# Maduino_Zero_Canbus_RS485_v1_1.net
KiCad netlist of a schematic drawn in EAGLE
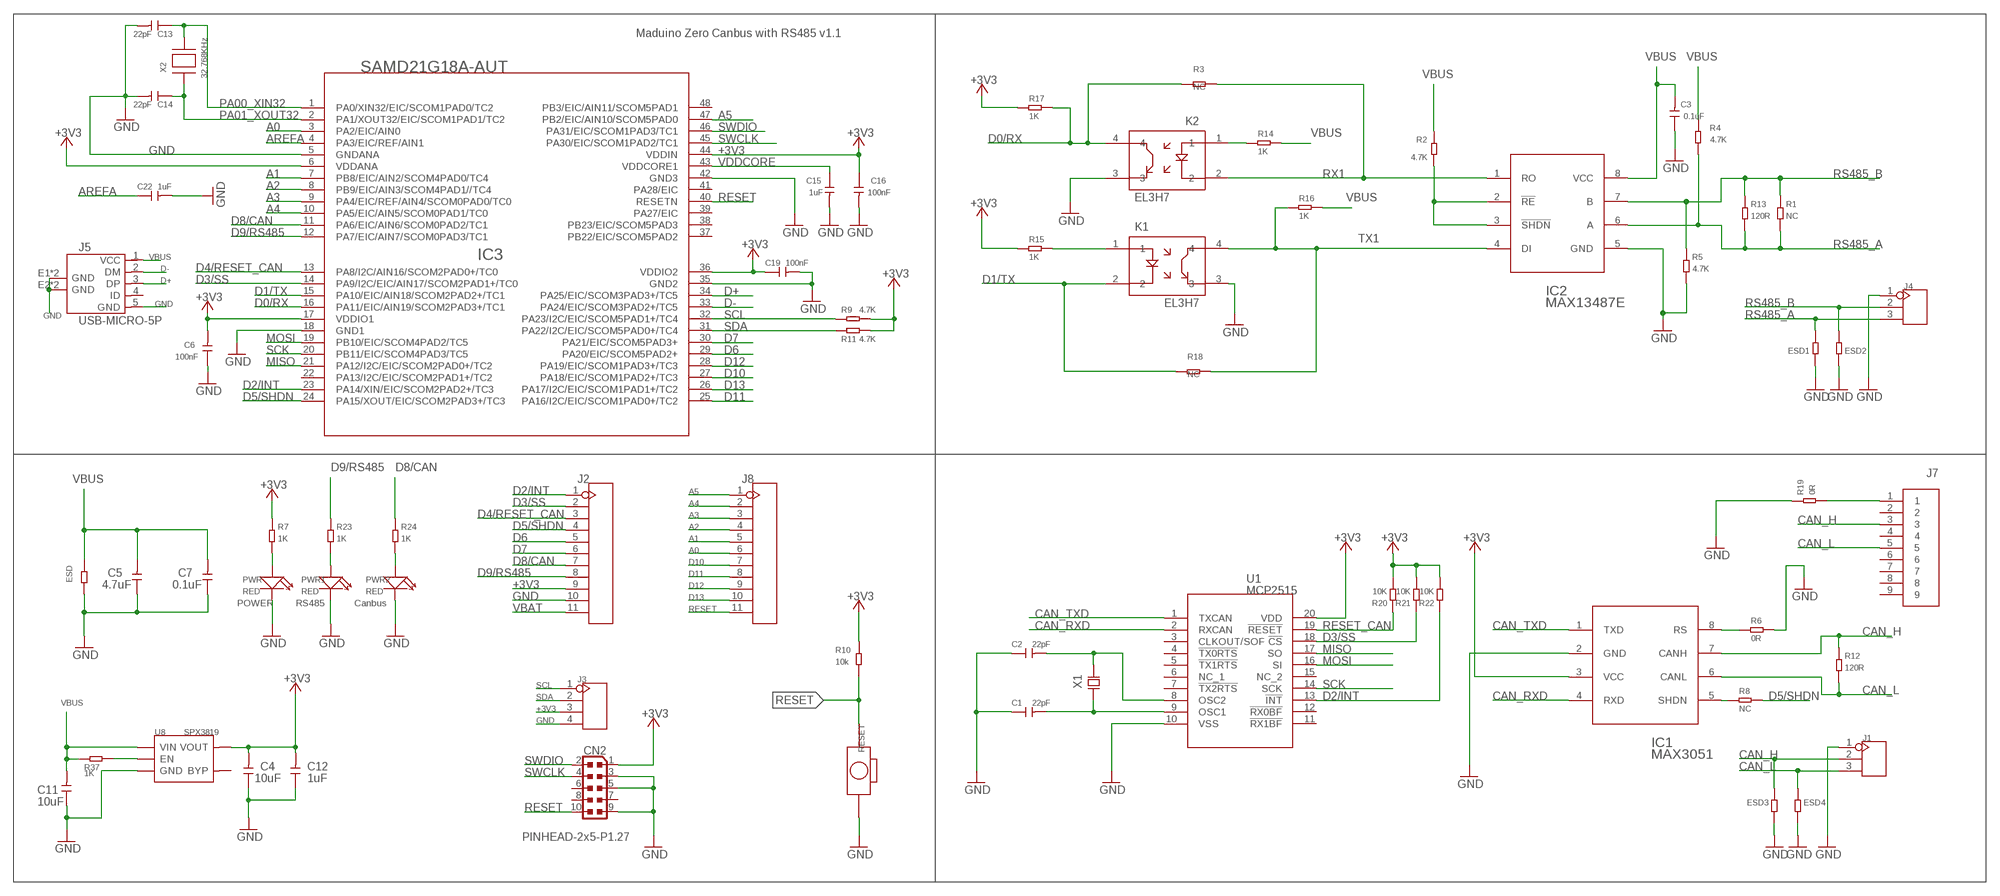
[diagram p0: schematic, sheet 1]

(export (version "E")
  (design (tool "Eeschema 10.0.6"))
  (components
    (comp (ref "C1")
      (value "22pF")
      (footprint "eagle-import:0603")
      (libsource (lib "eagle-import") (part "C-0603"))
    )
    (comp (ref "C2")
      (value "22pF")
      (footprint "eagle-import:0603")
      (libsource (lib "eagle-import") (part "C-0603"))
    )
    (comp (ref "C3")
      (value "0.1uF")
      (footprint "eagle-import:0603")
      (libsource (lib "eagle-import") (part "C-0603"))
    )
    (comp (ref "C4")
      (value "10uF")
      (footprint "eagle-import:0603")
      (libsource (lib "eagle-import") (part "C-0603"))
    )
    (comp (ref "C5")
      (value "4.7uF")
      (footprint "eagle-import:0603")
      (libsource (lib "eagle-import") (part "C-0603"))
    )
    (comp (ref "C6")
      (value "100nF")
      (footprint "eagle-import:0603")
      (libsource (lib "eagle-import") (part "C-0603"))
    )
    (comp (ref "C7")
      (value "0.1uF")
      (footprint "eagle-import:0603")
      (libsource (lib "eagle-import") (part "C-0603"))
    )
    (comp (ref "C11")
      (value "10uF")
      (footprint "eagle-import:0603")
      (libsource (lib "eagle-import") (part "C-0603"))
    )
    (comp (ref "C12")
      (value "1uF")
      (footprint "eagle-import:0603")
      (libsource (lib "eagle-import") (part "C-0603"))
    )
    (comp (ref "C13")
      (value "22pF")
      (footprint "eagle-import:0603")
      (libsource (lib "eagle-import") (part "C-0603"))
    )
    (comp (ref "C14")
      (value "22pF")
      (footprint "eagle-import:0603")
      (libsource (lib "eagle-import") (part "C-0603"))
    )
    (comp (ref "C15")
      (value "1uF")
      (footprint "eagle-import:0603")
      (libsource (lib "eagle-import") (part "C-0603"))
    )
    (comp (ref "C16")
      (value "100nF")
      (footprint "eagle-import:0603")
      (libsource (lib "eagle-import") (part "C-0603"))
    )
    (comp (ref "C19")
      (value "100nF")
      (footprint "eagle-import:0603")
      (libsource (lib "eagle-import") (part "C-0603"))
    )
    (comp (ref "C22")
      (value "1uF")
      (footprint "eagle-import:0603")
      (libsource (lib "eagle-import") (part "C-0603"))
    )
    (comp (ref "CN2")
      (value "PINHEAD-2x5-P1.27")
      (footprint "eagle-import:PINHEAD_2X05_127")
      (libsource (lib "eagle-import") (part "0171_PH127-205DF055G00AROUND-PADS"))
    )
    (comp (ref "ESD")
      (value "R-0603")
      (footprint "eagle-import:R0603")
      (libsource (lib "eagle-import") (part "R-0603"))
    )
    (comp (ref "ESD1")
      (value "R-0603")
      (footprint "eagle-import:R0603")
      (libsource (lib "eagle-import") (part "R-0603"))
    )
    (comp (ref "ESD2")
      (value "R-0603")
      (footprint "eagle-import:R0603")
      (libsource (lib "eagle-import") (part "R-0603"))
    )
    (comp (ref "ESD3")
      (value "NC")
      (footprint "eagle-import:R0603")
      (libsource (lib "eagle-import") (part "R-0603"))
    )
    (comp (ref "ESD4")
      (value "NC")
      (footprint "eagle-import:R0603")
      (libsource (lib "eagle-import") (part "R-0603"))
    )
    (comp (ref "IC1")
      (value "MAX3051")
      (footprint "eagle-import:DIP8_MX3051")
      (libsource (lib "eagle-import") (part "MAX3051"))
    )
    (comp (ref "IC2")
      (value "MAX13487E")
      (footprint "eagle-import:DIP8_MAX13487")
      (libsource (lib "eagle-import") (part "MAX13487E"))
    )
    (comp (ref "IC3")
      (value "SAMD21G18A-AUT")
      (footprint "eagle-import:TQFP48-7X7")
      (libsource (lib "eagle-import") (part "ATSAMD21G18A-AUT"))
    )
    (comp (ref "J1")
      (value "HEADER-3P-2.54")
      (footprint "eagle-import:3P-2.54")
      (libsource (lib "eagle-import") (part "HEADER-3P-2.54"))
    )
    (comp (ref "J2")
      (value "HEADER-11P-2.54")
      (footprint "eagle-import:11P-2.54")
      (libsource (lib "eagle-import") (part "HEADER-11P-2.54"))
    )
    (comp (ref "J3")
      (value "HEADER-4P-60/35MILROUND")
      (footprint "eagle-import:4P-65_35ROUND")
      (libsource (lib "eagle-import") (part "HEADER-4P-60/35MILROUND"))
    )
    (comp (ref "J4")
      (value "HEADER-3P-2.54")
      (footprint "eagle-import:3P-2.54")
      (libsource (lib "eagle-import") (part "HEADER-3P-2.54"))
    )
    (comp (ref "J5")
      (value "USB-MICRO-5P")
      (footprint "eagle-import:MICRO-USB-5P")
      (libsource (lib "eagle-import") (part "USB-MICRO-5P"))
    )
    (comp (ref "J7")
      (value "DB9-90")
      (footprint "eagle-import:DIP9-DB9-P2.77")
      (libsource (lib "eagle-import") (part "DB9-90"))
    )
    (comp (ref "J8")
      (value "HEADER-11P-2.54")
      (footprint "eagle-import:11P-2.54")
      (libsource (lib "eagle-import") (part "HEADER-11P-2.54"))
    )
    (comp (ref "K1")
      (value "EL3H7")
      (footprint "eagle-import:SOP-4_P1.27")
      (libsource (lib "eagle-import") (part "EL3H7"))
    )
    (comp (ref "K2")
      (value "EL3H7")
      (footprint "eagle-import:SOP-4_P1.27")
      (libsource (lib "eagle-import") (part "EL3H7"))
    )
    (comp (ref "PWR")
      (value "RED")
      (footprint "eagle-import:LED-0603")
      (libsource (lib "eagle-import") (part "LED'0603'"))
    )
    (comp (ref "PWR1")
      (value "RED")
      (footprint "eagle-import:LED-0603")
      (libsource (lib "eagle-import") (part "LED'0603'"))
    )
    (comp (ref "PWR2")
      (value "RED")
      (footprint "eagle-import:LED-0603")
      (libsource (lib "eagle-import") (part "LED'0603'"))
    )
    (comp (ref "R1")
      (value "NC")
      (footprint "eagle-import:R0603")
      (libsource (lib "eagle-import") (part "R-0603"))
    )
    (comp (ref "R2")
      (value "4.7K")
      (footprint "eagle-import:R0603")
      (libsource (lib "eagle-import") (part "R-0603"))
    )
    (comp (ref "R3")
      (value "NC")
      (footprint "eagle-import:R0603")
      (libsource (lib "eagle-import") (part "R-0603"))
    )
    (comp (ref "R4")
      (value "4.7K")
      (footprint "eagle-import:R0603")
      (libsource (lib "eagle-import") (part "R-0603"))
    )
    (comp (ref "R5")
      (value "4.7K")
      (footprint "eagle-import:R0603")
      (libsource (lib "eagle-import") (part "R-0603"))
    )
    (comp (ref "R6")
      (value "0R")
      (footprint "eagle-import:R0603")
      (libsource (lib "eagle-import") (part "R-0603"))
    )
    (comp (ref "R7")
      (value "1K")
      (footprint "eagle-import:R0603")
      (libsource (lib "eagle-import") (part "R-0603"))
    )
    (comp (ref "R8")
      (value "NC")
      (footprint "eagle-import:R0603")
      (libsource (lib "eagle-import") (part "R-0603"))
    )
    (comp (ref "R9")
      (value "4.7K")
      (footprint "eagle-import:R0603")
      (libsource (lib "eagle-import") (part "R-0603"))
    )
    (comp (ref "R10")
      (value "10k")
      (footprint "eagle-import:R0603")
      (libsource (lib "eagle-import") (part "R-0603"))
    )
    (comp (ref "R11")
      (value "4.7K")
      (footprint "eagle-import:R0603")
      (libsource (lib "eagle-import") (part "R-0603"))
    )
    (comp (ref "R12")
      (value "120R")
      (footprint "eagle-import:R0603")
      (libsource (lib "eagle-import") (part "R-0603"))
    )
    (comp (ref "R13")
      (value "120R")
      (footprint "eagle-import:R0603")
      (libsource (lib "eagle-import") (part "R-0603"))
    )
    (comp (ref "R14")
      (value "1K")
      (footprint "eagle-import:R0603")
      (libsource (lib "eagle-import") (part "R-0603"))
    )
    (comp (ref "R15")
      (value "1K")
      (footprint "eagle-import:R0603")
      (libsource (lib "eagle-import") (part "R-0603"))
    )
    (comp (ref "R16")
      (value "1K")
      (footprint "eagle-import:R0603")
      (libsource (lib "eagle-import") (part "R-0603"))
    )
    (comp (ref "R17")
      (value "1K")
      (footprint "eagle-import:R0603")
      (libsource (lib "eagle-import") (part "R-0603"))
    )
    (comp (ref "R18")
      (value "NC")
      (footprint "eagle-import:R0603")
      (libsource (lib "eagle-import") (part "R-0603"))
    )
    (comp (ref "R19")
      (value "0R")
      (footprint "eagle-import:R0603")
      (libsource (lib "eagle-import") (part "R-0603"))
    )
    (comp (ref "R20")
      (value "10K")
      (footprint "eagle-import:R0603")
      (libsource (lib "eagle-import") (part "R-0603"))
    )
    (comp (ref "R21")
      (value "10K")
      (footprint "eagle-import:R0603")
      (libsource (lib "eagle-import") (part "R-0603"))
    )
    (comp (ref "R22")
      (value "10K")
      (footprint "eagle-import:R0603")
      (libsource (lib "eagle-import") (part "R-0603"))
    )
    (comp (ref "R23")
      (value "1K")
      (footprint "eagle-import:R0603")
      (libsource (lib "eagle-import") (part "R-0603"))
    )
    (comp (ref "R24")
      (value "1K")
      (footprint "eagle-import:R0603")
      (libsource (lib "eagle-import") (part "R-0603"))
    )
    (comp (ref "R37")
      (value "1K")
      (footprint "eagle-import:R0603")
      (libsource (lib "eagle-import") (part "R-0603"))
    )
    (comp (ref "RESET")
      (value "BOTTON-2P-90D")
      (footprint "eagle-import:2P-7.62X3.56-90D")
      (libsource (lib "eagle-import") (part "BOTTON-2P-90D"))
    )
    (comp (ref "U1")
      (value "MCP2515")
      (footprint "eagle-import:SSOP-20")
      (libsource (lib "eagle-import") (part "MCP2515"))
    )
    (comp (ref "U8")
      (value "SPX3819")
      (footprint "eagle-import:SOT23-5")
      (libsource (lib "eagle-import") (part "SPX3819"))
    )
    (comp (ref "X1")
      (value "XTAL-8MHZ")
      (footprint "eagle-import:SMD-5032_2P_8M")
      (libsource (lib "eagle-import") (part "XTAL-8MHZ"))
    )
    (comp (ref "X2")
      (value "32.768KHz")
      (footprint "eagle-import:XTAL3215")
      (libsource (lib "eagle-import") (part "XTAL-3.2X1.5"))
    )
  )
  (nets
    (net (code "1") (name "+3V3") (class "Default")
      (node (ref "C12") (pin "2") (pinfunction "2_2") (pintype "passive"))
      (node (ref "C16") (pin "1") (pinfunction "1_1") (pintype "passive"))
      (node (ref "C19") (pin "1") (pinfunction "1_1") (pintype "passive"))
      (node (ref "C4") (pin "2") (pinfunction "2_2") (pintype "passive"))
      (node (ref "C6") (pin "2") (pinfunction "2_2") (pintype "passive"))
      (node (ref "CN2") (pin "1") (pinfunction "1_1") (pintype "passive"))
      (node (ref "IC1") (pin "3") (pinfunction "VCC_3") (pintype "bidirectional"))
      (node (ref "IC3") (pin "17") (pinfunction "VDDIO1_17") (pintype "power_in"))
      (node (ref "IC3") (pin "36") (pinfunction "VDDIO2_36") (pintype "power_in"))
      (node (ref "IC3") (pin "44") (pinfunction "VDDIN_44") (pintype "power_in"))
      (node (ref "IC3") (pin "6") (pinfunction "VDDANA_6") (pintype "power_in"))
      (node (ref "J2") (pin "9") (pinfunction "9_9") (pintype "bidirectional"))
      (node (ref "J3") (pin "3") (pinfunction "P$3_3") (pintype "bidirectional"))
      (node (ref "R10") (pin "2") (pinfunction "2_2") (pintype "passive"))
      (node (ref "R11") (pin "2") (pinfunction "2_2") (pintype "passive"))
      (node (ref "R15") (pin "2") (pinfunction "2_2") (pintype "passive"))
      (node (ref "R17") (pin "2") (pinfunction "2_2") (pintype "passive"))
      (node (ref "R20") (pin "1") (pinfunction "1_1") (pintype "passive"))
      (node (ref "R21") (pin "1") (pinfunction "1_1") (pintype "passive"))
      (node (ref "R22") (pin "1") (pinfunction "1_1") (pintype "passive"))
      (node (ref "R7") (pin "1") (pinfunction "1_1") (pintype "passive"))
      (node (ref "R9") (pin "2") (pinfunction "2_2") (pintype "passive"))
      (node (ref "U1") (pin "20") (pinfunction "VDD_20") (pintype "bidirectional"))
      (node (ref "U8") (pin "5") (pinfunction "VOUT_5") (pintype "bidirectional"))
    )
    (net (code "2") (name "/A0") (class "Default")
      (node (ref "IC3") (pin "3") (pinfunction "PA2/EIC/AIN0_3") (pintype "bidirectional"))
      (node (ref "J8") (pin "6") (pinfunction "6_6") (pintype "bidirectional"))
    )
    (net (code "3") (name "/A1") (class "Default")
      (node (ref "IC3") (pin "7") (pinfunction "PB8/EIC/AIN2/SCOM4PAD0/TC4_7") (pintype "bidirectional"))
      (node (ref "J8") (pin "5") (pinfunction "5_5") (pintype "bidirectional"))
    )
    (net (code "4") (name "/A2") (class "Default")
      (node (ref "IC3") (pin "8") (pinfunction "PB9/EIC/AIN3/SCOM4PAD1//TC4_8") (pintype "bidirectional"))
      (node (ref "J8") (pin "4") (pinfunction "4_4") (pintype "bidirectional"))
    )
    (net (code "5") (name "/A3") (class "Default")
      (node (ref "IC3") (pin "9") (pinfunction "PA4/EIC/REF/AIN4/SCOM0PAD0/TC0_9") (pintype "bidirectional"))
      (node (ref "J8") (pin "3") (pinfunction "3_3") (pintype "bidirectional"))
    )
    (net (code "6") (name "/A4") (class "Default")
      (node (ref "IC3") (pin "10") (pinfunction "PA5/EIC/AIN5/SCOM0PAD1/TC0_10") (pintype "bidirectional"))
      (node (ref "J8") (pin "2") (pinfunction "2_2") (pintype "bidirectional"))
    )
    (net (code "7") (name "/A5") (class "Default")
      (node (ref "IC3") (pin "47") (pinfunction "PB2/EIC/AIN10/SCOM5PAD0_47") (pintype "bidirectional"))
      (node (ref "J8") (pin "1") (pinfunction "1_1") (pintype "bidirectional"))
    )
    (net (code "8") (name "/AREFA") (class "Default")
      (node (ref "C22") (pin "1") (pinfunction "1_1") (pintype "passive"))
      (node (ref "IC3") (pin "4") (pinfunction "PA3/EIC/REF/AIN1_4") (pintype "bidirectional"))
    )
    (net (code "9") (name "/CAN_H") (class "Default")
      (node (ref "ESD3") (pin "1") (pinfunction "1_1") (pintype "passive"))
      (node (ref "IC1") (pin "7") (pinfunction "CANH_7") (pintype "bidirectional"))
      (node (ref "J1") (pin "2") (pinfunction "P$2_2") (pintype "bidirectional"))
      (node (ref "J7") (pin "3") (pinfunction "3_3") (pintype "bidirectional"))
      (node (ref "R12") (pin "1") (pinfunction "1_1") (pintype "passive"))
    )
    (net (code "10") (name "/CAN_L") (class "Default")
      (node (ref "ESD4") (pin "1") (pinfunction "1_1") (pintype "passive"))
      (node (ref "IC1") (pin "6") (pinfunction "CANL_6") (pintype "bidirectional"))
      (node (ref "J1") (pin "3") (pinfunction "P$3_3") (pintype "bidirectional"))
      (node (ref "J7") (pin "5") (pinfunction "5_5") (pintype "bidirectional"))
      (node (ref "R12") (pin "2") (pinfunction "2_2") (pintype "passive"))
    )
    (net (code "11") (name "/CAN_RXD") (class "Default")
      (node (ref "IC1") (pin "4") (pinfunction "RXD_4") (pintype "bidirectional"))
      (node (ref "U1") (pin "2") (pinfunction "RXCAN_2") (pintype "bidirectional"))
    )
    (net (code "12") (name "/CAN_TXD") (class "Default")
      (node (ref "IC1") (pin "1") (pinfunction "TXD_1") (pintype "bidirectional"))
      (node (ref "U1") (pin "1") (pinfunction "TXCAN_1") (pintype "bidirectional"))
    )
    (net (code "13") (name "/D+") (class "Default")
      (node (ref "IC3") (pin "34") (pinfunction "PA25/EIC/SCOM3PAD3+/TC5_34") (pintype "bidirectional"))
      (node (ref "J5") (pin "3") (pinfunction "DP_3") (pintype "bidirectional"))
    )
    (net (code "14") (name "/D-") (class "Default")
      (node (ref "IC3") (pin "33") (pinfunction "PA24/EIC/SCOM3PAD2+/TC5_33") (pintype "bidirectional"))
      (node (ref "J5") (pin "2") (pinfunction "DM_2") (pintype "bidirectional"))
    )
    (net (code "15") (name "/D0{slash}RX") (class "Default")
      (node (ref "IC3") (pin "16") (pinfunction "PA11/EIC/AIN19/SCOM2PAD3+/TC1_16") (pintype "bidirectional"))
      (node (ref "K2") (pin "4") (pinfunction "4_4") (pintype "bidirectional"))
      (node (ref "R17") (pin "1") (pinfunction "1_1") (pintype "passive"))
      (node (ref "R3") (pin "2") (pinfunction "2_2") (pintype "passive"))
    )
    (net (code "16") (name "/D1{slash}TX") (class "Default")
      (node (ref "IC3") (pin "15") (pinfunction "PA10/EIC/AIN18/SCOM2PAD2+/TC1_15") (pintype "bidirectional"))
      (node (ref "K1") (pin "2") (pinfunction "2_2") (pintype "bidirectional"))
      (node (ref "R18") (pin "2") (pinfunction "2_2") (pintype "passive"))
    )
    (net (code "17") (name "/D2{slash}INT") (class "Default")
      (node (ref "IC3") (pin "23") (pinfunction "PA14/XIN/EIC/SCOM2PAD2+/TC3_23") (pintype "bidirectional"))
      (node (ref "J2") (pin "1") (pinfunction "1_1") (pintype "bidirectional"))
      (node (ref "R22") (pin "2") (pinfunction "2_2") (pintype "passive"))
      (node (ref "U1") (pin "13") (pinfunction "~{INT}_13") (pintype "bidirectional"))
    )
    (net (code "18") (name "/D3{slash}SS") (class "Default")
      (node (ref "IC3") (pin "14") (pinfunction "PA9/I2C/EIC/AIN17/SCOM2PAD1+/TC0_14") (pintype "bidirectional"))
      (node (ref "J2") (pin "2") (pinfunction "2_2") (pintype "bidirectional"))
      (node (ref "R21") (pin "2") (pinfunction "2_2") (pintype "passive"))
      (node (ref "U1") (pin "18") (pinfunction "~{CS}_18") (pintype "bidirectional"))
    )
    (net (code "19") (name "/D4{slash}RESET_CAN") (class "Default")
      (node (ref "IC3") (pin "13") (pinfunction "PA8/I2C/AIN16/SCOM2PAD0+/TC0_13") (pintype "bidirectional"))
      (node (ref "J2") (pin "3") (pinfunction "3_3") (pintype "bidirectional"))
    )
    (net (code "20") (name "/D5{slash}SHDN") (class "Default")
      (node (ref "IC3") (pin "24") (pinfunction "PA15/XOUT/EIC/SCOM2PAD3+/TC3_24") (pintype "bidirectional"))
      (node (ref "J2") (pin "4") (pinfunction "4_4") (pintype "bidirectional"))
      (node (ref "R8") (pin "1") (pinfunction "1_1") (pintype "passive"))
    )
    (net (code "21") (name "/D6") (class "Default")
      (node (ref "IC3") (pin "29") (pinfunction "PA20/EIC/SCOM5PAD2+_29") (pintype "bidirectional"))
      (node (ref "J2") (pin "5") (pinfunction "5_5") (pintype "bidirectional"))
    )
    (net (code "22") (name "/D7") (class "Default")
      (node (ref "IC3") (pin "30") (pinfunction "PA21/EIC/SCOM5PAD3+_30") (pintype "bidirectional"))
      (node (ref "J2") (pin "6") (pinfunction "6_6") (pintype "bidirectional"))
    )
    (net (code "23") (name "/D8{slash}CAN") (class "Default")
      (node (ref "IC3") (pin "11") (pinfunction "PA6/EIC/AIN6/SCOM0PAD2/TC1_11") (pintype "bidirectional"))
      (node (ref "J2") (pin "7") (pinfunction "7_7") (pintype "bidirectional"))
      (node (ref "R24") (pin "1") (pinfunction "1_1") (pintype "passive"))
    )
    (net (code "24") (name "/D9{slash}RS485") (class "Default")
      (node (ref "IC3") (pin "12") (pinfunction "PA7/EIC/AIN7/SCOM0PAD3/TC1_12") (pintype "bidirectional"))
      (node (ref "J2") (pin "8") (pinfunction "8_8") (pintype "bidirectional"))
      (node (ref "R23") (pin "1") (pinfunction "1_1") (pintype "passive"))
    )
    (net (code "25") (name "/D10") (class "Default")
      (node (ref "IC3") (pin "27") (pinfunction "PA18/EIC/SCOM1PAD2+/TC3_27") (pintype "bidirectional"))
      (node (ref "J8") (pin "7") (pinfunction "7_7") (pintype "bidirectional"))
    )
    (net (code "26") (name "/D11") (class "Default")
      (node (ref "IC3") (pin "25") (pinfunction "PA16/I2C/EIC/SCOM1PAD0+/TC2_25") (pintype "bidirectional"))
      (node (ref "J8") (pin "8") (pinfunction "8_8") (pintype "bidirectional"))
    )
    (net (code "27") (name "/D12") (class "Default")
      (node (ref "IC3") (pin "28") (pinfunction "PA19/EIC/SCOM1PAD3+/TC3_28") (pintype "bidirectional"))
      (node (ref "J8") (pin "9") (pinfunction "9_9") (pintype "bidirectional"))
    )
    (net (code "28") (name "/D13") (class "Default")
      (node (ref "IC3") (pin "26") (pinfunction "PA17/I2C/EIC/SCOM1PAD1+/TC2_26") (pintype "bidirectional"))
      (node (ref "J8") (pin "10") (pinfunction "10_10") (pintype "bidirectional"))
    )
    (net (code "29") (name "/MISO") (class "Default")
      (node (ref "IC3") (pin "21") (pinfunction "PA12/I2C/EIC/SCOM2PAD0+/TC2_21") (pintype "bidirectional"))
      (node (ref "U1") (pin "17") (pinfunction "SO_17") (pintype "bidirectional"))
    )
    (net (code "30") (name "/MOSI") (class "Default")
      (node (ref "IC3") (pin "19") (pinfunction "PB10/EIC/SCOM4PAD2/TC5_19") (pintype "bidirectional"))
      (node (ref "U1") (pin "16") (pinfunction "SI_16") (pintype "bidirectional"))
    )
    (net (code "31") (name "/PA00_XIN32") (class "Default")
      (node (ref "C13") (pin "1") (pinfunction "1_1") (pintype "passive"))
      (node (ref "IC3") (pin "1") (pinfunction "PA0/XIN32/EIC/SCOM1PAD0/TC2_1") (pintype "bidirectional"))
      (node (ref "X2") (pin "P$2") (pinfunction "P$2_P$2") (pintype "bidirectional"))
    )
    (net (code "32") (name "/PA01_XOUT32") (class "Default")
      (node (ref "C14") (pin "1") (pinfunction "1_1") (pintype "passive"))
      (node (ref "IC3") (pin "2") (pinfunction "PA1/XOUT32/EIC/SCOM1PAD1/TC2_2") (pintype "bidirectional"))
      (node (ref "X2") (pin "P$1") (pinfunction "P$1_P$1") (pintype "bidirectional"))
    )
    (net (code "33") (name "/RESET_CAN") (class "Default")
      (node (ref "R20") (pin "2") (pinfunction "2_2") (pintype "passive"))
      (node (ref "U1") (pin "19") (pinfunction "~{RESET}_19") (pintype "bidirectional"))
    )
    (net (code "34") (name "/RS485_A") (class "Default")
      (node (ref "ESD1") (pin "2") (pinfunction "2_2") (pintype "passive"))
      (node (ref "IC2") (pin "6") (pinfunction "A_6") (pintype "bidirectional"))
      (node (ref "J4") (pin "3") (pinfunction "P$3_3") (pintype "bidirectional"))
      (node (ref "R1") (pin "1") (pinfunction "1_1") (pintype "passive"))
      (node (ref "R13") (pin "1") (pinfunction "1_1") (pintype "passive"))
      (node (ref "R4") (pin "1") (pinfunction "1_1") (pintype "passive"))
    )
    (net (code "35") (name "/RS485_B") (class "Default")
      (node (ref "ESD2") (pin "2") (pinfunction "2_2") (pintype "passive"))
      (node (ref "IC2") (pin "7") (pinfunction "B_7") (pintype "bidirectional"))
      (node (ref "J4") (pin "2") (pinfunction "P$2_2") (pintype "bidirectional"))
      (node (ref "R1") (pin "2") (pinfunction "2_2") (pintype "passive"))
      (node (ref "R13") (pin "2") (pinfunction "2_2") (pintype "passive"))
      (node (ref "R5") (pin "2") (pinfunction "2_2") (pintype "passive"))
    )
    (net (code "36") (name "/RX1") (class "Default")
      (node (ref "IC2") (pin "1") (pinfunction "RO_1") (pintype "bidirectional"))
      (node (ref "K2") (pin "2") (pinfunction "2_2") (pintype "bidirectional"))
      (node (ref "R3") (pin "1") (pinfunction "1_1") (pintype "passive"))
    )
    (net (code "37") (name "/SCK") (class "Default")
      (node (ref "IC3") (pin "20") (pinfunction "PB11/EIC/SCOM4PAD3/TC5_20") (pintype "bidirectional"))
      (node (ref "U1") (pin "14") (pinfunction "SCK_14") (pintype "bidirectional"))
    )
    (net (code "38") (name "/SCL") (class "Default")
      (node (ref "IC3") (pin "32") (pinfunction "PA23/I2C/EIC/SCOM5PAD1+/TC4_32") (pintype "bidirectional"))
      (node (ref "J3") (pin "1") (pinfunction "P$1_1") (pintype "bidirectional"))
      (node (ref "R9") (pin "1") (pinfunction "1_1") (pintype "passive"))
    )
    (net (code "39") (name "/SDA") (class "Default")
      (node (ref "IC3") (pin "31") (pinfunction "PA22/I2C/EIC/SCOM5PAD0+/TC4_31") (pintype "bidirectional"))
      (node (ref "J3") (pin "2") (pinfunction "P$2_2") (pintype "bidirectional"))
      (node (ref "R11") (pin "1") (pinfunction "1_1") (pintype "passive"))
    )
    (net (code "40") (name "/SWCLK") (class "Default")
      (node (ref "CN2") (pin "4") (pinfunction "4_4") (pintype "passive"))
      (node (ref "IC3") (pin "45") (pinfunction "PA30/EIC/SCOM1PAD2/TC1_45") (pintype "bidirectional"))
    )
    (net (code "41") (name "/SWDIO") (class "Default")
      (node (ref "CN2") (pin "2") (pinfunction "2_2") (pintype "passive"))
      (node (ref "IC3") (pin "46") (pinfunction "PA31/EIC/SCOM1PAD3/TC1_46") (pintype "bidirectional"))
    )
    (net (code "42") (name "/TX1") (class "Default")
      (node (ref "IC2") (pin "4") (pinfunction "DI_4") (pintype "bidirectional"))
      (node (ref "K1") (pin "4") (pinfunction "4_4") (pintype "bidirectional"))
      (node (ref "R16") (pin "2") (pinfunction "2_2") (pintype "passive"))
      (node (ref "R18") (pin "1") (pinfunction "1_1") (pintype "passive"))
    )
    (net (code "43") (name "/VBAT") (class "Default")
      (node (ref "J2") (pin "11") (pinfunction "11_11") (pintype "bidirectional"))
    )
    (net (code "44") (name "/VBUS") (class "Default")
      (node (ref "C11") (pin "2") (pinfunction "2_2") (pintype "passive"))
      (node (ref "C3") (pin "2") (pinfunction "2_2") (pintype "passive"))
      (node (ref "C5") (pin "2") (pinfunction "2_2") (pintype "passive"))
      (node (ref "C7") (pin "2") (pinfunction "2_2") (pintype "passive"))
      (node (ref "ESD") (pin "1") (pinfunction "1_1") (pintype "passive"))
      (node (ref "IC2") (pin "8") (pinfunction "VCC_8") (pintype "bidirectional"))
      (node (ref "J5") (pin "1") (pinfunction "VCC_1") (pintype "bidirectional"))
      (node (ref "R14") (pin "1") (pinfunction "1_1") (pintype "passive"))
      (node (ref "R16") (pin "1") (pinfunction "1_1") (pintype "passive"))
      (node (ref "R2") (pin "2") (pinfunction "2_2") (pintype "passive"))
      (node (ref "R37") (pin "1") (pinfunction "1_1") (pintype "passive"))
      (node (ref "R4") (pin "2") (pinfunction "2_2") (pintype "passive"))
      (node (ref "U8") (pin "1") (pinfunction "VIN_1") (pintype "bidirectional"))
    )
    (net (code "45") (name "/VDDCORE") (class "Default")
      (node (ref "C15") (pin "1") (pinfunction "1_1") (pintype "passive"))
      (node (ref "IC3") (pin "43") (pinfunction "VDDCORE1_43") (pintype "input"))
    )
    (net (code "46") (name "GND") (class "Default")
      (node (ref "C1") (pin "1") (pinfunction "1_1") (pintype "passive"))
      (node (ref "C11") (pin "1") (pinfunction "1_1") (pintype "passive"))
      (node (ref "C12") (pin "1") (pinfunction "1_1") (pintype "passive"))
      (node (ref "C13") (pin "2") (pinfunction "2_2") (pintype "passive"))
      (node (ref "C14") (pin "2") (pinfunction "2_2") (pintype "passive"))
      (node (ref "C15") (pin "2") (pinfunction "2_2") (pintype "passive"))
      (node (ref "C16") (pin "2") (pinfunction "2_2") (pintype "passive"))
      (node (ref "C19") (pin "2") (pinfunction "2_2") (pintype "passive"))
      (node (ref "C2") (pin "1") (pinfunction "1_1") (pintype "passive"))
      (node (ref "C22") (pin "2") (pinfunction "2_2") (pintype "passive"))
      (node (ref "C3") (pin "1") (pinfunction "1_1") (pintype "passive"))
      (node (ref "C4") (pin "1") (pinfunction "1_1") (pintype "passive"))
      (node (ref "C5") (pin "1") (pinfunction "1_1") (pintype "passive"))
      (node (ref "C6") (pin "1") (pinfunction "1_1") (pintype "passive"))
      (node (ref "C7") (pin "1") (pinfunction "1_1") (pintype "passive"))
      (node (ref "CN2") (pin "3") (pinfunction "3_3") (pintype "passive"))
      (node (ref "CN2") (pin "5") (pinfunction "5_5") (pintype "passive"))
      (node (ref "CN2") (pin "9") (pinfunction "9_9") (pintype "passive"))
      (node (ref "ESD") (pin "2") (pinfunction "2_2") (pintype "passive"))
      (node (ref "ESD1") (pin "1") (pinfunction "1_1") (pintype "passive"))
      (node (ref "ESD2") (pin "1") (pinfunction "1_1") (pintype "passive"))
      (node (ref "ESD3") (pin "2") (pinfunction "2_2") (pintype "passive"))
      (node (ref "ESD4") (pin "2") (pinfunction "2_2") (pintype "passive"))
      (node (ref "IC1") (pin "2") (pinfunction "GND_2") (pintype "bidirectional"))
      (node (ref "IC2") (pin "5") (pinfunction "GND_5") (pintype "bidirectional"))
      (node (ref "IC3") (pin "18") (pinfunction "GND1_18") (pintype "power_in"))
      (node (ref "IC3") (pin "35") (pinfunction "GND2_35") (pintype "power_in"))
      (node (ref "IC3") (pin "42") (pinfunction "GND3_42") (pintype "power_in"))
      (node (ref "IC3") (pin "5") (pinfunction "GNDANA_5") (pintype "power_in"))
      (node (ref "J1") (pin "1") (pinfunction "P$1_1") (pintype "bidirectional"))
      (node (ref "J2") (pin "10") (pinfunction "10_10") (pintype "bidirectional"))
      (node (ref "J3") (pin "4") (pinfunction "P$4_4") (pintype "bidirectional"))
      (node (ref "J4") (pin "1") (pinfunction "P$1_1") (pintype "bidirectional"))
      (node (ref "J5") (pin "5") (pinfunction "GND_5") (pintype "bidirectional"))
      (node (ref "J5") (pin "E1") (pinfunction "GND_E1") (pintype "bidirectional"))
      (node (ref "J5") (pin "E2") (pinfunction "GND_E2") (pintype "bidirectional"))
      (node (ref "J5") (pin "P1") (pinfunction "GND_P1") (pintype "bidirectional"))
      (node (ref "J5") (pin "P2") (pinfunction "GND_P2") (pintype "bidirectional"))
      (node (ref "K1") (pin "3") (pinfunction "3_3") (pintype "bidirectional"))
      (node (ref "K2") (pin "3") (pinfunction "3_3") (pintype "bidirectional"))
      (node (ref "PWR") (pin "-") (pinfunction "-_-") (pintype "passive"))
      (node (ref "PWR1") (pin "-") (pinfunction "-_-") (pintype "passive"))
      (node (ref "PWR2") (pin "-") (pinfunction "-_-") (pintype "passive"))
      (node (ref "R19") (pin "2") (pinfunction "2_2") (pintype "passive"))
      (node (ref "R5") (pin "1") (pinfunction "1_1") (pintype "passive"))
      (node (ref "R6") (pin "1") (pinfunction "1_1") (pintype "passive"))
      (node (ref "RESET") (pin "P$2") (pinfunction "2_P$2") (pintype "bidirectional"))
      (node (ref "U1") (pin "10") (pinfunction "VSS_10") (pintype "bidirectional"))
      (node (ref "U8") (pin "2") (pinfunction "GND_2") (pintype "bidirectional"))
    )
    (net (code "47") (name "Net-(IC1-RS)") (class "Default")
      (node (ref "IC1") (pin "8") (pinfunction "RS_8") (pintype "bidirectional"))
      (node (ref "R6") (pin "2") (pinfunction "2_2") (pintype "passive"))
    )
    (net (code "48") (name "Net-(IC1-SHDN)") (class "Default")
      (node (ref "IC1") (pin "5") (pinfunction "SHDN_5") (pintype "bidirectional"))
      (node (ref "R8") (pin "2") (pinfunction "2_2") (pintype "passive"))
    )
    (net (code "49") (name "Net-(IC2-~{RE})") (class "Default")
      (node (ref "IC2") (pin "2") (pinfunction "~{RE}_2") (pintype "bidirectional"))
      (node (ref "IC2") (pin "3") (pinfunction "~{SHDN}_3") (pintype "bidirectional"))
      (node (ref "R2") (pin "1") (pinfunction "1_1") (pintype "passive"))
    )
    (net (code "50") (name "Net-(J7-Pad1)") (class "Default")
      (node (ref "J7") (pin "1") (pinfunction "1_1") (pintype "bidirectional"))
      (node (ref "R19") (pin "1") (pinfunction "1_1") (pintype "passive"))
    )
    (net (code "51") (name "Net-(K1-Pad1)") (class "Default")
      (node (ref "K1") (pin "1") (pinfunction "1_1") (pintype "bidirectional"))
      (node (ref "R15") (pin "1") (pinfunction "1_1") (pintype "passive"))
    )
    (net (code "52") (name "Net-(K2-Pad1)") (class "Default")
      (node (ref "K2") (pin "1") (pinfunction "1_1") (pintype "bidirectional"))
      (node (ref "R14") (pin "2") (pinfunction "2_2") (pintype "passive"))
    )
    (net (code "53") (name "Net-(PWR-Pad+)") (class "Default")
      (node (ref "PWR") (pin "+") (pinfunction "+_+") (pintype "passive"))
      (node (ref "R7") (pin "2") (pinfunction "2_2") (pintype "passive"))
    )
    (net (code "54") (name "Net-(PWR1-Pad+)") (class "Default")
      (node (ref "PWR1") (pin "+") (pinfunction "+_+") (pintype "passive"))
      (node (ref "R23") (pin "2") (pinfunction "2_2") (pintype "passive"))
    )
    (net (code "55") (name "Net-(PWR2-Pad+)") (class "Default")
      (node (ref "PWR2") (pin "+") (pinfunction "+_+") (pintype "passive"))
      (node (ref "R24") (pin "2") (pinfunction "2_2") (pintype "passive"))
    )
    (net (code "56") (name "Net-(U1-OSC1)") (class "Default")
      (node (ref "C1") (pin "2") (pinfunction "2_2") (pintype "passive"))
      (node (ref "U1") (pin "9") (pinfunction "OSC1_9") (pintype "bidirectional"))
      (node (ref "X1") (pin "1") (pinfunction "1_1") (pintype "bidirectional"))
    )
    (net (code "57") (name "Net-(U1-OSC2)") (class "Default")
      (node (ref "C2") (pin "2") (pinfunction "2_2") (pintype "passive"))
      (node (ref "U1") (pin "8") (pinfunction "OSC2_8") (pintype "bidirectional"))
      (node (ref "X1") (pin "2") (pinfunction "2_2") (pintype "bidirectional"))
    )
    (net (code "58") (name "Net-(U8-EN)") (class "Default")
      (node (ref "R37") (pin "2") (pinfunction "2_2") (pintype "passive"))
      (node (ref "U8") (pin "3") (pinfunction "EN_3") (pintype "bidirectional"))
    )
    (net (code "59") (name "RESET") (class "Default")
      (node (ref "CN2") (pin "10") (pinfunction "10_10") (pintype "passive"))
      (node (ref "IC3") (pin "40") (pinfunction "RESETN_40") (pintype "bidirectional"))
      (node (ref "J8") (pin "11") (pinfunction "11_11") (pintype "bidirectional"))
      (node (ref "R10") (pin "1") (pinfunction "1_1") (pintype "passive"))
      (node (ref "RESET") (pin "P$1") (pinfunction "1_P$1") (pintype "bidirectional"))
    )
    (net (code "60") (name "unconnected-(CN2-Pad6)") (class "Default")
      (node (ref "CN2") (pin "6") (pinfunction "6_6") (pintype "passive"))
    )
    (net (code "61") (name "unconnected-(CN2-Pad7)") (class "Default")
      (node (ref "CN2") (pin "7") (pinfunction "7_7") (pintype "passive"))
    )
    (net (code "62") (name "unconnected-(CN2-Pad8)") (class "Default")
      (node (ref "CN2") (pin "8") (pinfunction "8_8") (pintype "passive"))
    )
    (net (code "63") (name "unconnected-(IC3-PA13{slash}I2C{slash}EIC{slash}SCOM2PAD1+{slash}TC2-Pad22)") (class "Default")
      (node (ref "IC3") (pin "22") (pinfunction "PA13/I2C/EIC/SCOM2PAD1+/TC2_22") (pintype "bidirectional"))
    )
    (net (code "64") (name "unconnected-(IC3-PA27{slash}EIC-Pad39)") (class "Default")
      (node (ref "IC3") (pin "39") (pinfunction "PA27/EIC_39") (pintype "bidirectional"))
    )
    (net (code "65") (name "unconnected-(IC3-PA28{slash}EIC-Pad41)") (class "Default")
      (node (ref "IC3") (pin "41") (pinfunction "PA28/EIC_41") (pintype "bidirectional"))
    )
    (net (code "66") (name "unconnected-(IC3-PB3{slash}EIC{slash}AIN11{slash}SCOM5PAD1-Pad48)") (class "Default")
      (node (ref "IC3") (pin "48") (pinfunction "PB3/EIC/AIN11/SCOM5PAD1_48") (pintype "bidirectional"))
    )
    (net (code "67") (name "unconnected-(IC3-PB22{slash}EIC{slash}SCOM5PAD2-Pad37)") (class "Default")
      (node (ref "IC3") (pin "37") (pinfunction "PB22/EIC/SCOM5PAD2_37") (pintype "bidirectional"))
    )
    (net (code "68") (name "unconnected-(IC3-PB23{slash}EIC{slash}SCOM5PAD3-Pad38)") (class "Default")
      (node (ref "IC3") (pin "38") (pinfunction "PB23/EIC/SCOM5PAD3_38") (pintype "bidirectional"))
    )
    (net (code "69") (name "unconnected-(J5-ID-Pad4)") (class "Default")
      (node (ref "J5") (pin "4") (pinfunction "ID_4") (pintype "bidirectional"))
    )
    (net (code "70") (name "unconnected-(J7-Pad2)") (class "Default")
      (node (ref "J7") (pin "2") (pinfunction "2_2") (pintype "bidirectional"))
    )
    (net (code "71") (name "unconnected-(J7-Pad4)") (class "Default")
      (node (ref "J7") (pin "4") (pinfunction "4_4") (pintype "bidirectional"))
    )
    (net (code "72") (name "unconnected-(J7-Pad6)") (class "Default")
      (node (ref "J7") (pin "6") (pinfunction "6_6") (pintype "bidirectional"))
    )
    (net (code "73") (name "unconnected-(J7-Pad7)") (class "Default")
      (node (ref "J7") (pin "7") (pinfunction "7_7") (pintype "bidirectional"))
    )
    (net (code "74") (name "unconnected-(J7-Pad8)") (class "Default")
      (node (ref "J7") (pin "8") (pinfunction "8_8") (pintype "bidirectional"))
    )
    (net (code "75") (name "unconnected-(J7-Pad9)") (class "Default")
      (node (ref "J7") (pin "9") (pinfunction "9_9") (pintype "bidirectional"))
    )
    (net (code "76") (name "unconnected-(U1-CLKOUT{slash}SOF-Pad3)") (class "Default")
      (node (ref "U1") (pin "3") (pinfunction "CLKOUT/SOF_3") (pintype "bidirectional"))
    )
    (net (code "77") (name "unconnected-(U1-NC_1-Pad6)") (class "Default")
      (node (ref "U1") (pin "6") (pinfunction "NC_1_6") (pintype "bidirectional"))
    )
    (net (code "78") (name "unconnected-(U1-NC_2-Pad15)") (class "Default")
      (node (ref "U1") (pin "15") (pinfunction "NC_2_15") (pintype "bidirectional"))
    )
    (net (code "79") (name "unconnected-(U1-~{RX0BF}-Pad12)") (class "Default")
      (node (ref "U1") (pin "12") (pinfunction "~{RX0BF}_12") (pintype "bidirectional"))
    )
    (net (code "80") (name "unconnected-(U1-~{RX1BF}-Pad11)") (class "Default")
      (node (ref "U1") (pin "11") (pinfunction "~{RX1BF}_11") (pintype "bidirectional"))
    )
    (net (code "81") (name "unconnected-(U1-~{TX0RTS}-Pad4)") (class "Default")
      (node (ref "U1") (pin "4") (pinfunction "~{TX0RTS}_4") (pintype "bidirectional"))
    )
    (net (code "82") (name "unconnected-(U1-~{TX1RTS}-Pad5)") (class "Default")
      (node (ref "U1") (pin "5") (pinfunction "~{TX1RTS}_5") (pintype "bidirectional"))
    )
    (net (code "83") (name "unconnected-(U1-~{TX2RTS}-Pad7)") (class "Default")
      (node (ref "U1") (pin "7") (pinfunction "~{TX2RTS}_7") (pintype "bidirectional"))
    )
    (net (code "84") (name "unconnected-(U8-BYP-Pad4)") (class "Default")
      (node (ref "U8") (pin "4") (pinfunction "BYP_4") (pintype "bidirectional"))
    )
  )
)
